# go_sign.net
KiCad netlist of a schematic drawn in Altium Designer
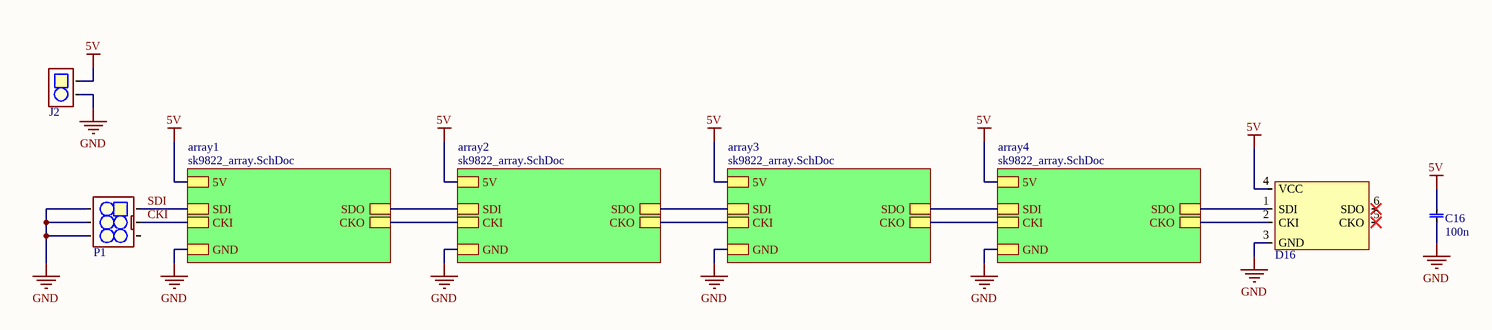
[diagram p0: go_sign.SchDoc]

(export (version "E")
  (design (tool "Eeschema 10.0.6"))
  (components
    (comp (ref "C16")
      (value "100n")
      (footprint "0603 cap")
      (fields (field (name "Comment") "0603, capacitor"))
      (libsource (lib "sign_lib") (part "0603, capacitor"))
    )
    (comp (ref "D16")
      (value "Neo - SK9822")
      (footprint "SK9822_FLIPPED")
      (libsource (lib "sign_lib") (part "Neo - SK9822"))
    )
    (comp (ref "J2")
      (value "2 Pole MSTBA Connector")
      (footprint "2POLE_MSTBA")
      (libsource (lib "sign_lib") (part "2 Pole MSTBA Connector"))
    )
    (comp (ref "P1")
      (value "2x3 Pin Header")
      (footprint "2x3 PH")
      (description "2x3 Ribbon connector")
      (libsource (lib "sign_lib") (part "2x3 Ribbon connector"))
    )
  )
  (nets
    (net (code "1") (name "/CKI") (class "Default")
      (node (ref "P1") (pin "2") (pinfunction "2_2") (pintype "passive"))
    )
    (net (code "5") (name "/CKO") (class "Default")
      (node (ref "D16") (pin "2") (pinfunction "CKI_2") (pintype "passive"))
    )
    (net (code "6") (name "/SDI") (class "Default")
      (node (ref "P1") (pin "1") (pinfunction "1_1") (pintype "passive"))
    )
    (net (code "10") (name "/SDO") (class "Default")
      (node (ref "D16") (pin "1") (pinfunction "SDI_1") (pintype "passive"))
    )
    (net (code "11") (name "5V") (class "Default")
      (node (ref "C16") (pin "1") (pinfunction "1_1") (pintype "passive"))
      (node (ref "D16") (pin "4") (pinfunction "VCC_4") (pintype "passive"))
      (node (ref "J2") (pin "1") (pinfunction "1_1") (pintype "passive"))
    )
    (net (code "12") (name "GND") (class "Default")
      (node (ref "C16") (pin "0") (pinfunction "0_0") (pintype "passive"))
      (node (ref "D16") (pin "3") (pinfunction "GND_3") (pintype "passive"))
      (node (ref "J2") (pin "2") (pinfunction "2_2") (pintype "passive"))
      (node (ref "P1") (pin "4") (pinfunction "4_4") (pintype "passive"))
      (node (ref "P1") (pin "5") (pinfunction "5_5") (pintype "passive"))
      (node (ref "P1") (pin "6") (pinfunction "6_6") (pintype "passive"))
    )
    (net (code "13") (name "unconnected-(D16-CKO-Pad5)") (class "Default")
      (node (ref "D16") (pin "5") (pinfunction "CKO_5") (pintype "passive+no_connect"))
    )
    (net (code "14") (name "unconnected-(D16-SDO-Pad6)") (class "Default")
      (node (ref "D16") (pin "6") (pinfunction "SDO_6") (pintype "passive+no_connect"))
    )
    (net (code "15") (name "unconnected-(P1-Pad3)") (class "Default")
      (node (ref "P1") (pin "3") (pinfunction "3_3") (pintype "passive"))
    )
  )
)
